# TELM0003_TempSense_BCR.net
KiCad netlist of a schematic drawn in Altium Designer
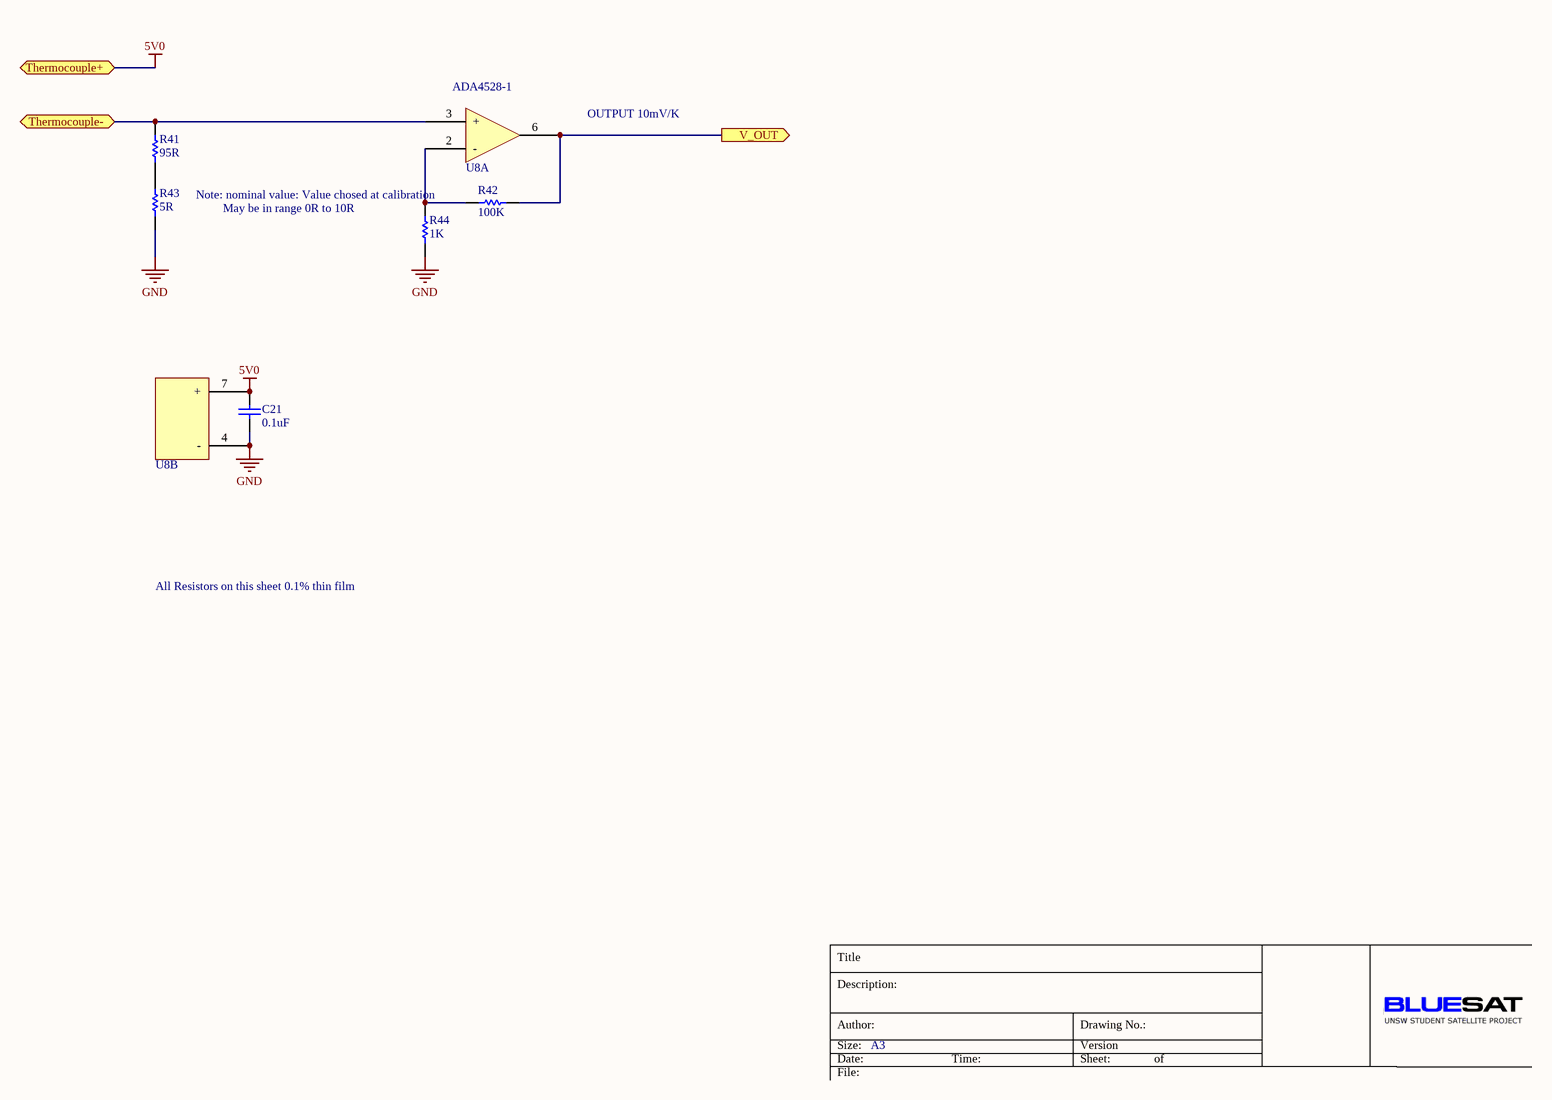
[diagram p0: TELM0003_TempSense_BCR.SchDoc]

(export (version "E")
  (design (tool "Eeschema 10.0.6"))
  (components
    (comp (ref "C21")
      (value "0.1uF")
      (footprint "CAPC2012M")
      (description "Capacitor")
      (fields (field (name "Comment") "Cap") (field (name "PUBLISHER") "Altium Limited"))
      (libsource (lib "Miscellaneous Devices") (part "Cap"))
    )
    (comp (ref "R41")
      (value "95R")
      (footprint "RESC2012M")
      (description "Resistor")
      (fields (field (name "Comment") "0805 Resistor") (field (name "PUBLISHER") "Altium Limited"))
      (libsource (lib "Miscellaneous Devices") (part "Res1"))
    )
    (comp (ref "R42")
      (value "100K")
      (footprint "RESC2012M")
      (description "Resistor")
      (fields (field (name "Comment") "0805 Resistor") (field (name "PUBLISHER") "Altium Limited"))
      (libsource (lib "Miscellaneous Devices") (part "Res1"))
    )
    (comp (ref "R43")
      (value "5R")
      (footprint "RESC2012M")
      (description "Resistor")
      (fields (field (name "Comment") "0805 Resistor") (field (name "PUBLISHER") "Altium Limited"))
      (libsource (lib "Miscellaneous Devices") (part "Res1"))
    )
    (comp (ref "R44")
      (value "1K")
      (footprint "RESC2012M")
      (description "Resistor")
      (fields (field (name "Comment") "0805 Resistor") (field (name "PUBLISHER") "Altium Limited"))
      (libsource (lib "Miscellaneous Devices") (part "Res1"))
    )
    (comp (ref "U8")
      (value "ADA4528-1")
      (footprint "SOIC8 - LME49720")
      (description "Dual, High Performance Audio Operational Amplifier")
      (libsource (lib "Schlib1") (part "ADA4528-1"))
    )
  )
  (nets
    (net (code "1") (name "/Thermocouple-") (class "Default")
      (node (ref "R41") (pin "1") (pinfunction "1_1") (pintype "passive"))
      (node (ref "U8") (pin "3") (pinfunction "+_3") (pintype "passive"))
    )
    (net (code "2") (name "/V_OUT") (class "Default")
      (node (ref "R42") (pin "2") (pinfunction "2_2") (pintype "passive"))
      (node (ref "U8") (pin "6") (pinfunction "Out_6") (pintype "passive"))
    )
    (net (code "3") (name "5V0") (class "Default")
      (node (ref "C21") (pin "1") (pinfunction "1_1") (pintype "passive"))
      (node (ref "U8") (pin "7") (pinfunction "+_7") (pintype "power_in"))
    )
    (net (code "4") (name "GND") (class "Default")
      (node (ref "C21") (pin "2") (pinfunction "2_2") (pintype "passive"))
      (node (ref "R43") (pin "2") (pinfunction "2_2") (pintype "passive"))
      (node (ref "R44") (pin "2") (pinfunction "2_2") (pintype "passive"))
      (node (ref "U8") (pin "4") (pinfunction "-_4") (pintype "power_in"))
    )
    (net (code "5") (name "Net-(R41-Pad2)") (class "Default")
      (node (ref "R41") (pin "2") (pinfunction "2_2") (pintype "passive"))
      (node (ref "R43") (pin "1") (pinfunction "1_1") (pintype "passive"))
    )
    (net (code "6") (name "Net-(U8A--)") (class "Default")
      (node (ref "R42") (pin "1") (pinfunction "1_1") (pintype "passive"))
      (node (ref "R44") (pin "1") (pinfunction "1_1") (pintype "passive"))
      (node (ref "U8") (pin "2") (pinfunction "-_2") (pintype "passive"))
    )
  )
)
